# oled_pmic.net
KiCad netlist of a schematic drawn in EAGLE
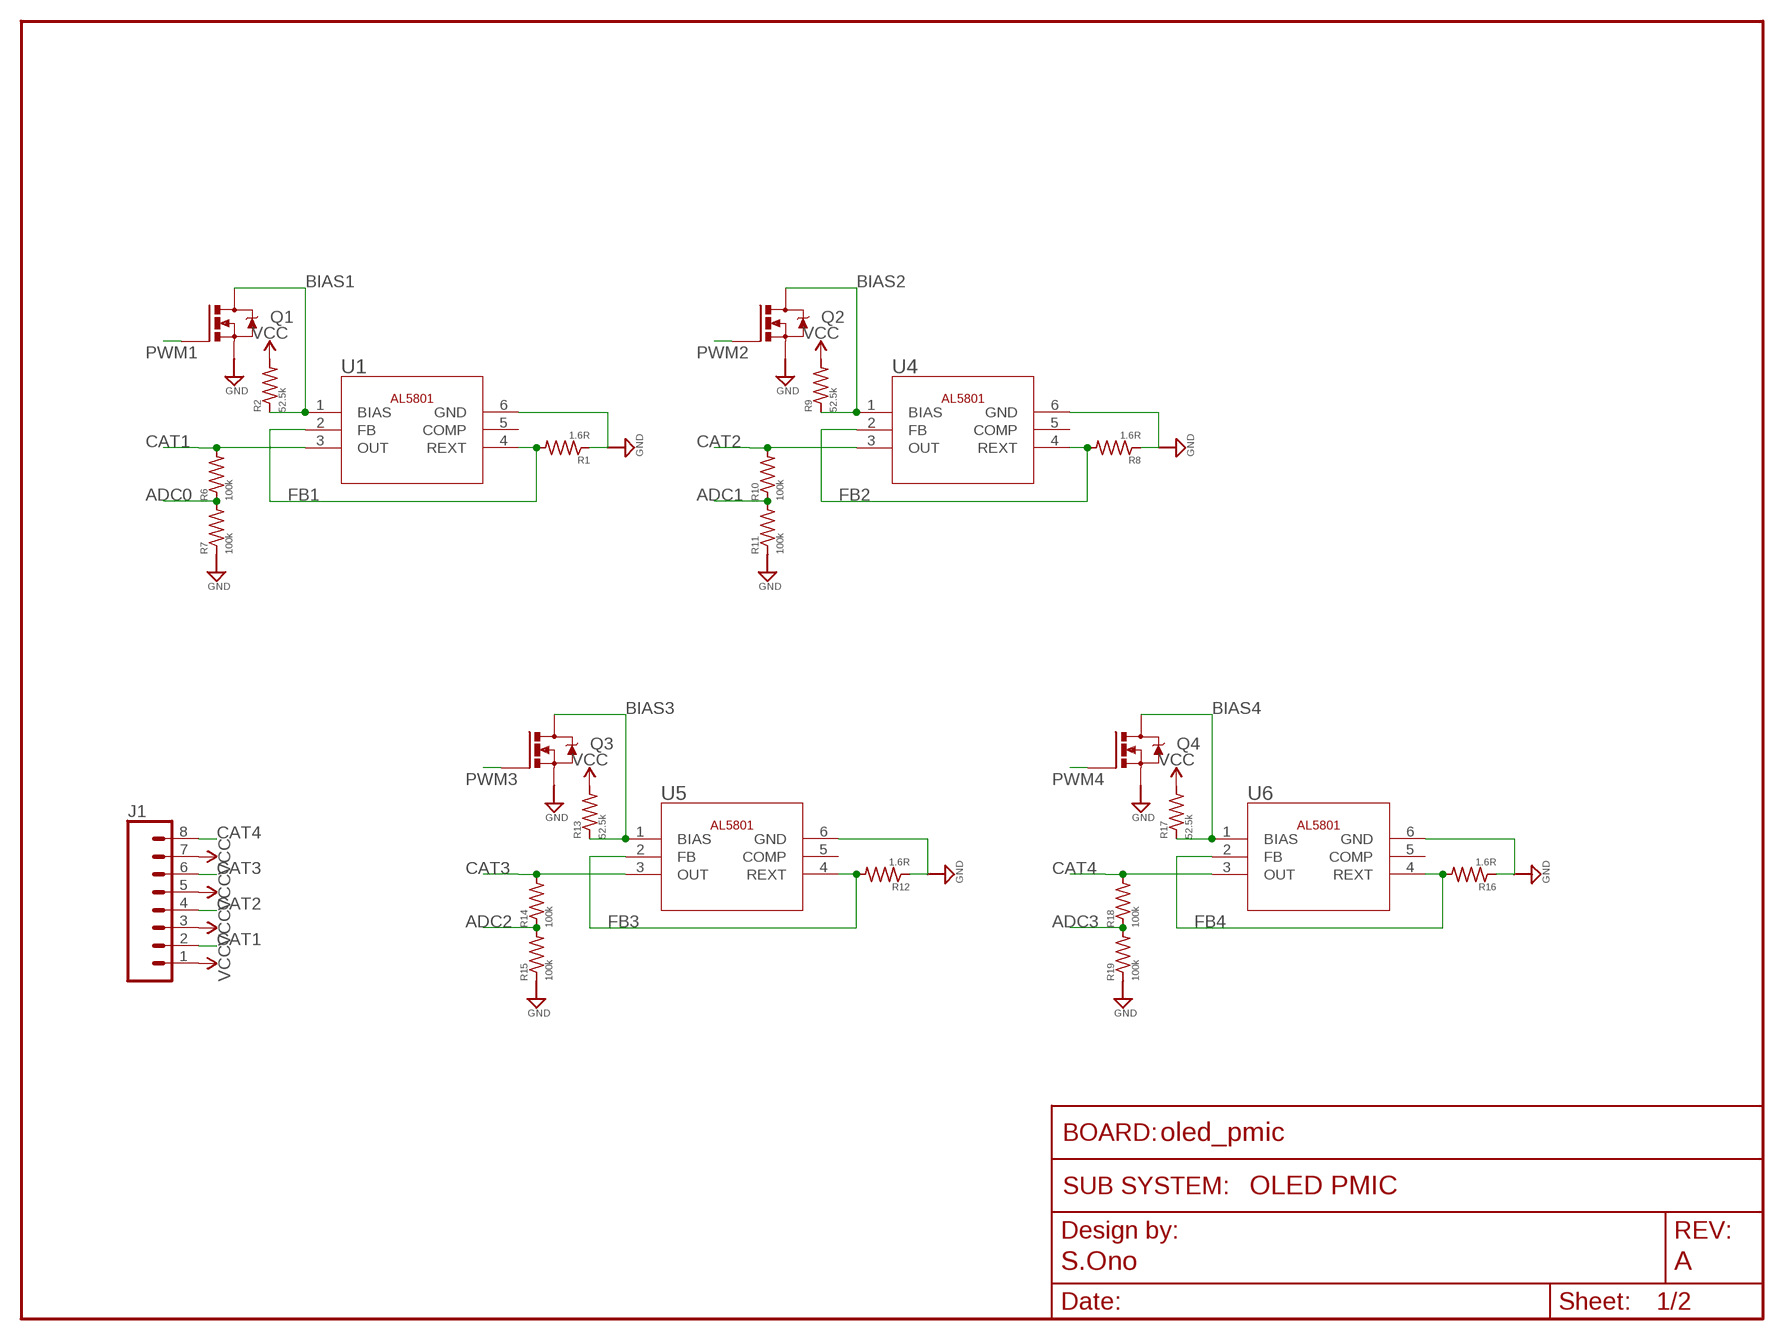
[diagram p0: schematic, sheet 1]
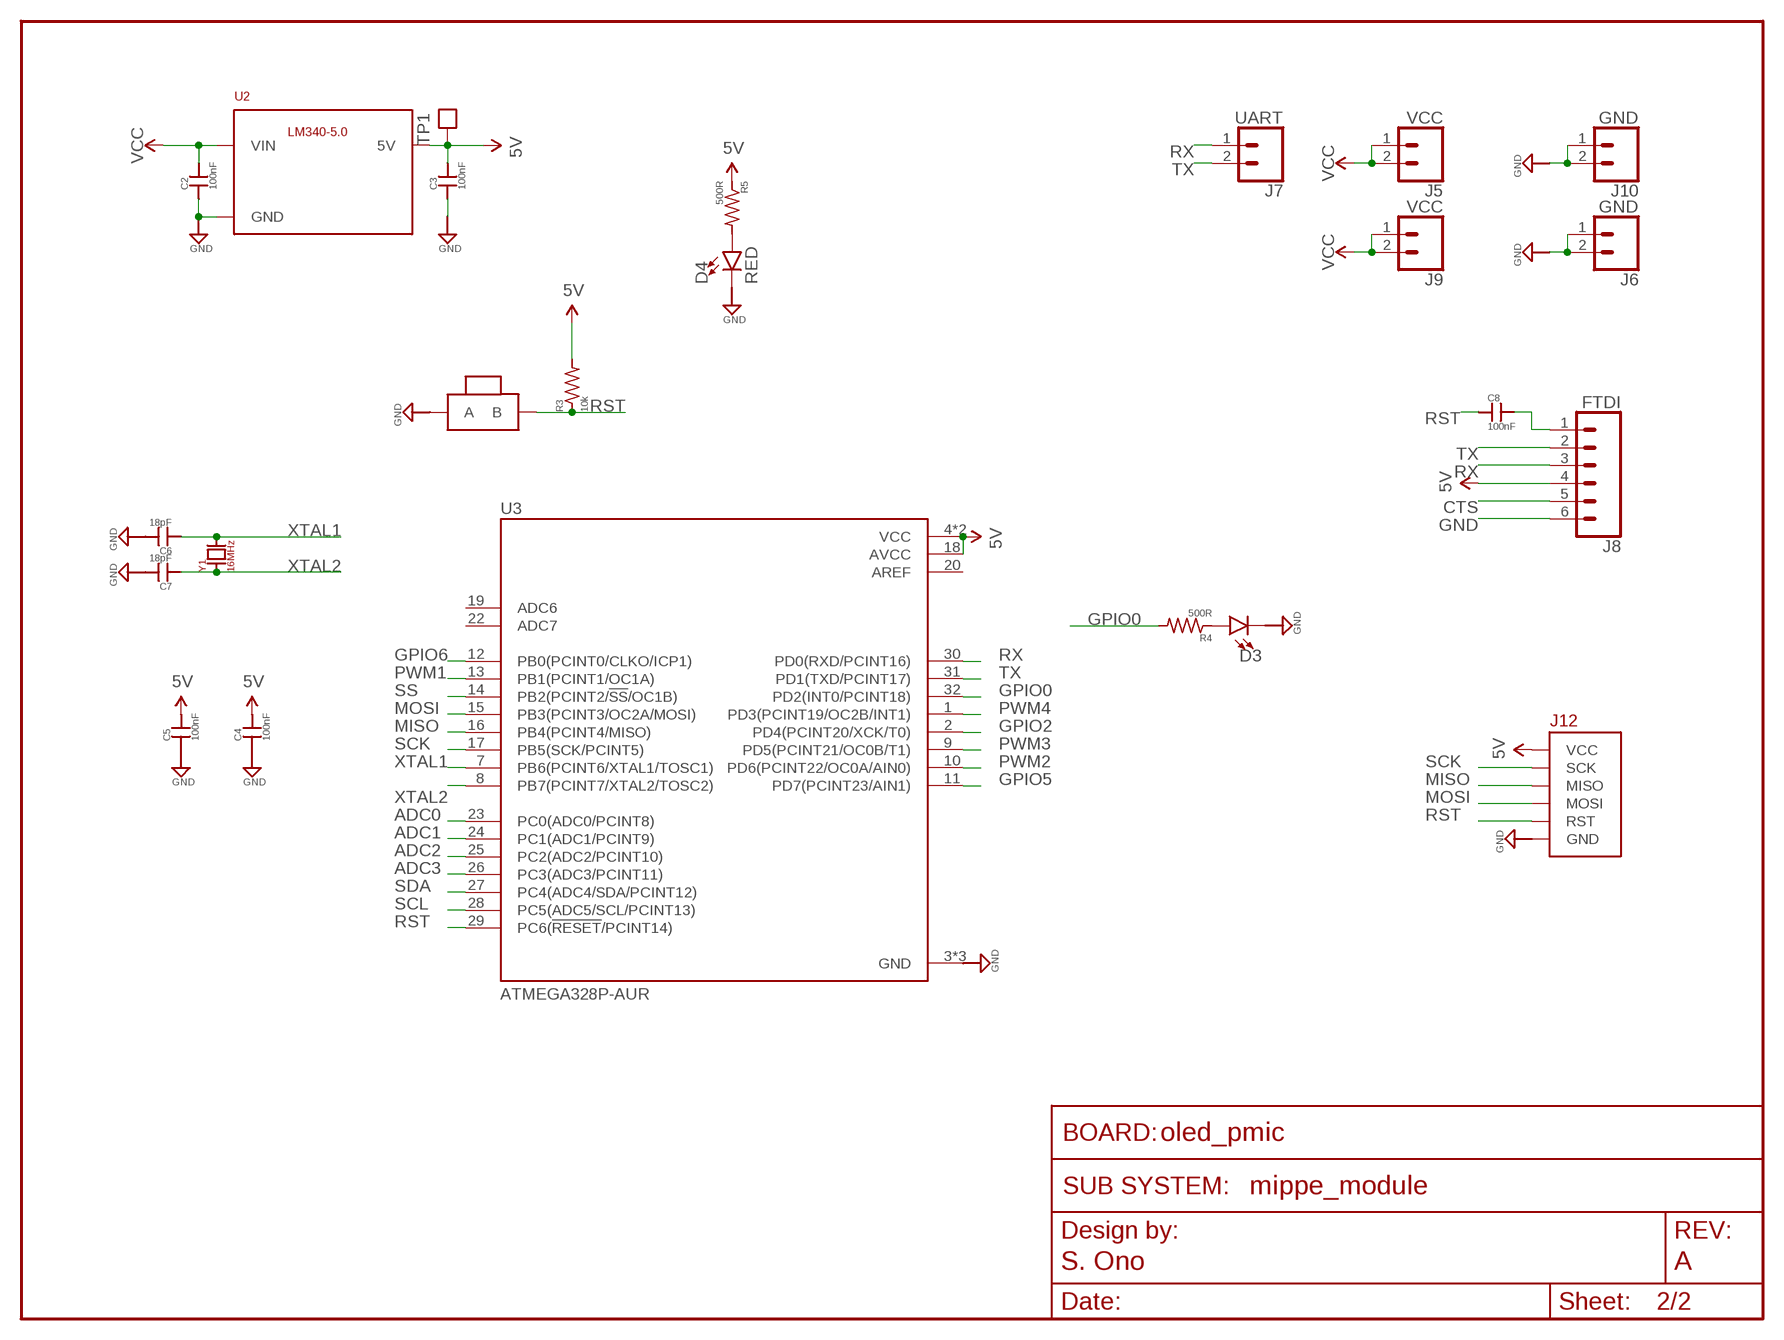
[diagram p1: schematic, sheet 2]

(export (version "E")
  (design (tool "Eeschema 10.0.6"))
  (components
    (comp (ref "C2")
      (value "100nF")
      (footprint "eagle-import:0402-CAP")
      (libsource (lib "eagle-import") (part "CAP0402-CAP"))
    )
    (comp (ref "C3")
      (value "100nF")
      (footprint "eagle-import:0402-CAP")
      (libsource (lib "eagle-import") (part "CAP0402-CAP"))
    )
    (comp (ref "C4")
      (value "100nF")
      (footprint "eagle-import:0402-CAP")
      (libsource (lib "eagle-import") (part "CAP0402-CAP"))
    )
    (comp (ref "C5")
      (value "100nF")
      (footprint "eagle-import:0402-CAP")
      (libsource (lib "eagle-import") (part "CAP0402-CAP"))
    )
    (comp (ref "C6")
      (value "18pF")
      (footprint "eagle-import:0402-CAP")
      (libsource (lib "eagle-import") (part "CAP0402-CAP"))
    )
    (comp (ref "C7")
      (value "18pF")
      (footprint "eagle-import:0402-CAP")
      (libsource (lib "eagle-import") (part "CAP0402-CAP"))
    )
    (comp (ref "C8")
      (value "100nF")
      (footprint "eagle-import:0402-CAP")
      (libsource (lib "eagle-import") (part "CAP0402-CAP"))
    )
    (comp (ref "D3")
      (value "LED0603")
      (footprint "eagle-import:LED-0603")
      (libsource (lib "eagle-import") (part "LED0603"))
    )
    (comp (ref "D4")
      (value "RED")
      (footprint "eagle-import:LED-0603")
      (libsource (lib "eagle-import") (part "LED0603"))
    )
    (comp (ref "J5")
      (value "VCC")
      (footprint "eagle-import:1X02")
      (libsource (lib "eagle-import") (part "CONN_02"))
    )
    (comp (ref "J6")
      (value "GND")
      (footprint "eagle-import:1X02")
      (libsource (lib "eagle-import") (part "CONN_02"))
    )
    (comp (ref "J7")
      (value "UART")
      (footprint "eagle-import:1X02")
      (libsource (lib "eagle-import") (part "CONN_02"))
    )
    (comp (ref "J8")
      (value "FTDI")
      (footprint "eagle-import:1X06_NO_SILK")
      (libsource (lib "eagle-import") (part "CONN_06NO_SILK_FEMALE_PTH"))
    )
    (comp (ref "J9")
      (value "VCC")
      (footprint "eagle-import:1X02")
      (libsource (lib "eagle-import") (part "CONN_02"))
    )
    (comp (ref "J10")
      (value "GND")
      (footprint "eagle-import:1X02")
      (libsource (lib "eagle-import") (part "CONN_02"))
    )
    (comp (ref "J12")
      (value "BURNIN")
      (footprint "eagle-import:BURNIN")
      (libsource (lib "eagle-import") (part "BURNIN"))
    )
    (comp (ref "R3")
      (value "10k")
      (footprint "eagle-import:R0402")
      (libsource (lib "eagle-import") (part "R-US_R0402"))
    )
    (comp (ref "R4")
      (value "500R")
      (footprint "eagle-import:R0402")
      (libsource (lib "eagle-import") (part "R-US_R0402"))
    )
    (comp (ref "R5")
      (value "500R")
      (footprint "eagle-import:R0402")
      (libsource (lib "eagle-import") (part "R-US_R0402"))
    )
    (comp (ref "SW1")
      (value "BTN-PTS810")
      (footprint "eagle-import:BTN_PTS810")
      (libsource (lib "eagle-import") (part "BTN-PTS810"))
    )
    (comp (ref "TP1")
      (value "TEST_POINTTHRU")
      (footprint "eagle-import:TEST_POINT")
      (libsource (lib "eagle-import") (part "TEST_POINTTHRU"))
    )
    (comp (ref "U2")
      (value "LM340MPX-5.0230")
      (footprint "eagle-import:SOT230P700X180-4N")
      (libsource (lib "eagle-import") (part "LM340MPX-5.0230"))
    )
    (comp (ref "U3")
      (value "ATMEGA328P-AUR")
      (footprint "eagle-import:QFP80P900X900X120-32N")
      (fields (field (name "DIGI-KEY_PART_NUMBER") "ATMEGA328P-AURCT-ND") (field (name "MF") "Microchip"))
      (libsource (lib "eagle-import") (part "ATMEGA328P-AUR"))
    )
    (comp (ref "Y1")
      (value "16MHz")
      (footprint "eagle-import:XTAL500X320X130N")
      (libsource (lib "eagle-import") (part "CRYSTAL_SMOL"))
    )
    (comp (ref "J1")
      (value "CONN_08\"")
      (footprint "eagle-import:1X08")
      (libsource (lib "eagle-import") (part "CONN_08{dblquote}"))
    )
    (comp (ref "Q1")
      (value "N-CHANNEL-MOSFETSOT23-3")
      (footprint "eagle-import:SOT23-3")
      (libsource (lib "eagle-import") (part "N-CHANNEL-MOSFETSOT23-3"))
    )
    (comp (ref "Q2")
      (value "N-CHANNEL-MOSFETSOT23-3")
      (footprint "eagle-import:SOT23-3")
      (libsource (lib "eagle-import") (part "N-CHANNEL-MOSFETSOT23-3"))
    )
    (comp (ref "Q3")
      (value "N-CHANNEL-MOSFETSOT23-3")
      (footprint "eagle-import:SOT23-3")
      (libsource (lib "eagle-import") (part "N-CHANNEL-MOSFETSOT23-3"))
    )
    (comp (ref "Q4")
      (value "N-CHANNEL-MOSFETSOT23-3")
      (footprint "eagle-import:SOT23-3")
      (libsource (lib "eagle-import") (part "N-CHANNEL-MOSFETSOT23-3"))
    )
    (comp (ref "R1")
      (value "1.6R")
      (footprint "eagle-import:0603-RES")
      (libsource (lib "eagle-import") (part "R-US_0603"))
    )
    (comp (ref "R2")
      (value "52.5k")
      (footprint "eagle-import:0603-RES")
      (libsource (lib "eagle-import") (part "R-US_0603"))
    )
    (comp (ref "R6")
      (value "100k")
      (footprint "eagle-import:R0402")
      (libsource (lib "eagle-import") (part "R-US_R0402"))
    )
    (comp (ref "R7")
      (value "100k")
      (footprint "eagle-import:R0402")
      (libsource (lib "eagle-import") (part "R-US_R0402"))
    )
    (comp (ref "R8")
      (value "1.6R")
      (footprint "eagle-import:0603-RES")
      (libsource (lib "eagle-import") (part "R-US_0603"))
    )
    (comp (ref "R9")
      (value "52.5k")
      (footprint "eagle-import:0603-RES")
      (libsource (lib "eagle-import") (part "R-US_0603"))
    )
    (comp (ref "R10")
      (value "100k")
      (footprint "eagle-import:R0402")
      (libsource (lib "eagle-import") (part "R-US_R0402"))
    )
    (comp (ref "R11")
      (value "100k")
      (footprint "eagle-import:R0402")
      (libsource (lib "eagle-import") (part "R-US_R0402"))
    )
    (comp (ref "R12")
      (value "1.6R")
      (footprint "eagle-import:0603-RES")
      (libsource (lib "eagle-import") (part "R-US_0603"))
    )
    (comp (ref "R13")
      (value "52.5k")
      (footprint "eagle-import:0603-RES")
      (libsource (lib "eagle-import") (part "R-US_0603"))
    )
    (comp (ref "R14")
      (value "100k")
      (footprint "eagle-import:R0402")
      (libsource (lib "eagle-import") (part "R-US_R0402"))
    )
    (comp (ref "R15")
      (value "100k")
      (footprint "eagle-import:R0402")
      (libsource (lib "eagle-import") (part "R-US_R0402"))
    )
    (comp (ref "R16")
      (value "1.6R")
      (footprint "eagle-import:0603-RES")
      (libsource (lib "eagle-import") (part "R-US_0603"))
    )
    (comp (ref "R17")
      (value "52.5k")
      (footprint "eagle-import:0603-RES")
      (libsource (lib "eagle-import") (part "R-US_0603"))
    )
    (comp (ref "R18")
      (value "100k")
      (footprint "eagle-import:R0402")
      (libsource (lib "eagle-import") (part "R-US_R0402"))
    )
    (comp (ref "R19")
      (value "100k")
      (footprint "eagle-import:R0402")
      (libsource (lib "eagle-import") (part "R-US_R0402"))
    )
    (comp (ref "U1")
      (value "AL5801W6-7")
      (footprint "eagle-import:SOT26")
      (libsource (lib "eagle-import") (part "AL5801W6-7"))
    )
    (comp (ref "U4")
      (value "AL5801W6-7")
      (footprint "eagle-import:SOT26")
      (libsource (lib "eagle-import") (part "AL5801W6-7"))
    )
    (comp (ref "U5")
      (value "AL5801W6-7")
      (footprint "eagle-import:SOT26")
      (libsource (lib "eagle-import") (part "AL5801W6-7"))
    )
    (comp (ref "U6")
      (value "AL5801W6-7")
      (footprint "eagle-import:SOT26")
      (libsource (lib "eagle-import") (part "AL5801W6-7"))
    )
  )
  (nets
    (net (code "1") (name "5V") (class "Default")
      (node (ref "C3") (pin "2") (pinfunction "2_2") (pintype "passive"))
      (node (ref "C4") (pin "2") (pinfunction "2_2") (pintype "passive"))
      (node (ref "C5") (pin "2") (pinfunction "2_2") (pintype "passive"))
      (node (ref "J12") (pin "3.3V") (pinfunction "VCC_3.3V") (pintype "power_in"))
      (node (ref "J8") (pin "4") (pinfunction "4_4") (pintype "passive"))
      (node (ref "R3") (pin "2") (pinfunction "2_2") (pintype "passive"))
      (node (ref "R5") (pin "1") (pinfunction "1_1") (pintype "passive"))
      (node (ref "TP1") (pin "1") (pinfunction "P$1_1") (pintype "bidirectional"))
      (node (ref "U2") (pin "3") (pinfunction "5V_3") (pintype "power_in"))
      (node (ref "U3") (pin "18") (pinfunction "AVCC_18") (pintype "power_in"))
      (node (ref "U3") (pin "4") (pinfunction "VCC_4") (pintype "power_in"))
      (node (ref "U3") (pin "6") (pinfunction "VCC_6") (pintype "power_in"))
    )
    (net (code "2") (name "ADC0") (class "Default")
      (node (ref "R6") (pin "1") (pinfunction "1_1") (pintype "passive"))
      (node (ref "R7") (pin "2") (pinfunction "2_2") (pintype "passive"))
      (node (ref "U3") (pin "23") (pinfunction "PC0(ADC0/PCINT8)_23") (pintype "bidirectional"))
    )
    (net (code "3") (name "ADC1") (class "Default")
      (node (ref "R10") (pin "1") (pinfunction "1_1") (pintype "passive"))
      (node (ref "R11") (pin "2") (pinfunction "2_2") (pintype "passive"))
      (node (ref "U3") (pin "24") (pinfunction "PC1(ADC1/PCINT9)_24") (pintype "bidirectional"))
    )
    (net (code "4") (name "ADC2") (class "Default")
      (node (ref "R14") (pin "1") (pinfunction "1_1") (pintype "passive"))
      (node (ref "R15") (pin "2") (pinfunction "2_2") (pintype "passive"))
      (node (ref "U3") (pin "25") (pinfunction "PC2(ADC2/PCINT10)_25") (pintype "bidirectional"))
    )
    (net (code "5") (name "ADC3") (class "Default")
      (node (ref "R18") (pin "1") (pinfunction "1_1") (pintype "passive"))
      (node (ref "R19") (pin "2") (pinfunction "2_2") (pintype "passive"))
      (node (ref "U3") (pin "26") (pinfunction "PC3(ADC3/PCINT11)_26") (pintype "bidirectional"))
    )
    (net (code "6") (name "AREF") (class "Default")
      (node (ref "U3") (pin "20") (pinfunction "AREF_20") (pintype "power_in"))
    )
    (net (code "7") (name "BIAS1") (class "Default")
      (node (ref "Q1") (pin "3") (pinfunction "D_3") (pintype "passive"))
      (node (ref "R2") (pin "1") (pinfunction "1_1") (pintype "passive"))
      (node (ref "U1") (pin "1") (pinfunction "BIAS_1") (pintype "output"))
    )
    (net (code "8") (name "BIAS2") (class "Default")
      (node (ref "Q2") (pin "3") (pinfunction "D_3") (pintype "passive"))
      (node (ref "R9") (pin "1") (pinfunction "1_1") (pintype "passive"))
      (node (ref "U4") (pin "1") (pinfunction "BIAS_1") (pintype "output"))
    )
    (net (code "9") (name "BIAS3") (class "Default")
      (node (ref "Q3") (pin "3") (pinfunction "D_3") (pintype "passive"))
      (node (ref "R13") (pin "1") (pinfunction "1_1") (pintype "passive"))
      (node (ref "U5") (pin "1") (pinfunction "BIAS_1") (pintype "output"))
    )
    (net (code "10") (name "BIAS4") (class "Default")
      (node (ref "Q4") (pin "3") (pinfunction "D_3") (pintype "passive"))
      (node (ref "R17") (pin "1") (pinfunction "1_1") (pintype "passive"))
      (node (ref "U6") (pin "1") (pinfunction "BIAS_1") (pintype "output"))
    )
    (net (code "11") (name "CAT1") (class "Default")
      (node (ref "J1") (pin "2") (pinfunction "2_2") (pintype "passive"))
      (node (ref "R6") (pin "2") (pinfunction "2_2") (pintype "passive"))
      (node (ref "U1") (pin "3") (pinfunction "OUT_3") (pintype "output"))
    )
    (net (code "12") (name "CAT2") (class "Default")
      (node (ref "J1") (pin "4") (pinfunction "4_4") (pintype "passive"))
      (node (ref "R10") (pin "2") (pinfunction "2_2") (pintype "passive"))
      (node (ref "U4") (pin "3") (pinfunction "OUT_3") (pintype "output"))
    )
    (net (code "13") (name "CAT3") (class "Default")
      (node (ref "J1") (pin "6") (pinfunction "6_6") (pintype "passive"))
      (node (ref "R14") (pin "2") (pinfunction "2_2") (pintype "passive"))
      (node (ref "U5") (pin "3") (pinfunction "OUT_3") (pintype "output"))
    )
    (net (code "14") (name "CAT4") (class "Default")
      (node (ref "J1") (pin "8") (pinfunction "8_8") (pintype "passive"))
      (node (ref "R18") (pin "2") (pinfunction "2_2") (pintype "passive"))
      (node (ref "U6") (pin "3") (pinfunction "OUT_3") (pintype "output"))
    )
    (net (code "15") (name "CTS") (class "Default")
      (node (ref "J8") (pin "5") (pinfunction "5_5") (pintype "passive"))
    )
    (net (code "16") (name "FB1") (class "Default")
      (node (ref "R1") (pin "2") (pinfunction "2_2") (pintype "passive"))
      (node (ref "U1") (pin "2") (pinfunction "FB_2") (pintype "passive"))
      (node (ref "U1") (pin "4") (pinfunction "REXT_4") (pintype "passive"))
    )
    (net (code "17") (name "FB2") (class "Default")
      (node (ref "R8") (pin "2") (pinfunction "2_2") (pintype "passive"))
      (node (ref "U4") (pin "2") (pinfunction "FB_2") (pintype "passive"))
      (node (ref "U4") (pin "4") (pinfunction "REXT_4") (pintype "passive"))
    )
    (net (code "18") (name "FB3") (class "Default")
      (node (ref "R12") (pin "2") (pinfunction "2_2") (pintype "passive"))
      (node (ref "U5") (pin "2") (pinfunction "FB_2") (pintype "passive"))
      (node (ref "U5") (pin "4") (pinfunction "REXT_4") (pintype "passive"))
    )
    (net (code "19") (name "FB4") (class "Default")
      (node (ref "R16") (pin "2") (pinfunction "2_2") (pintype "passive"))
      (node (ref "U6") (pin "2") (pinfunction "FB_2") (pintype "passive"))
      (node (ref "U6") (pin "4") (pinfunction "REXT_4") (pintype "passive"))
    )
    (net (code "20") (name "GND") (class "Default")
      (node (ref "C2") (pin "1") (pinfunction "1_1") (pintype "passive"))
      (node (ref "C3") (pin "1") (pinfunction "1_1") (pintype "passive"))
      (node (ref "C4") (pin "1") (pinfunction "1_1") (pintype "passive"))
      (node (ref "C5") (pin "1") (pinfunction "1_1") (pintype "passive"))
      (node (ref "C6") (pin "2") (pinfunction "2_2") (pintype "passive"))
      (node (ref "C7") (pin "2") (pinfunction "2_2") (pintype "passive"))
      (node (ref "D3") (pin "C") (pinfunction "C_C") (pintype "passive"))
      (node (ref "D4") (pin "C") (pinfunction "C_C") (pintype "passive"))
      (node (ref "J10") (pin "1") (pinfunction "1_1") (pintype "passive"))
      (node (ref "J10") (pin "2") (pinfunction "2_2") (pintype "passive"))
      (node (ref "J12") (pin "GND") (pinfunction "GND_GND") (pintype "power_in"))
      (node (ref "J6") (pin "1") (pinfunction "1_1") (pintype "passive"))
      (node (ref "J6") (pin "2") (pinfunction "2_2") (pintype "passive"))
      (node (ref "J8") (pin "6") (pinfunction "6_6") (pintype "passive"))
      (node (ref "Q1") (pin "2") (pinfunction "S_2") (pintype "passive"))
      (node (ref "Q2") (pin "2") (pinfunction "S_2") (pintype "passive"))
      (node (ref "Q3") (pin "2") (pinfunction "S_2") (pintype "passive"))
      (node (ref "Q4") (pin "2") (pinfunction "S_2") (pintype "passive"))
      (node (ref "R1") (pin "1") (pinfunction "1_1") (pintype "passive"))
      (node (ref "R11") (pin "1") (pinfunction "1_1") (pintype "passive"))
      (node (ref "R12") (pin "1") (pinfunction "1_1") (pintype "passive"))
      (node (ref "R15") (pin "1") (pinfunction "1_1") (pintype "passive"))
      (node (ref "R16") (pin "1") (pinfunction "1_1") (pintype "passive"))
      (node (ref "R19") (pin "1") (pinfunction "1_1") (pintype "passive"))
      (node (ref "R7") (pin "1") (pinfunction "1_1") (pintype "passive"))
      (node (ref "R8") (pin "1") (pinfunction "1_1") (pintype "passive"))
      (node (ref "SW1") (pin "1") (pinfunction "A_1") (pintype "bidirectional"))
      (node (ref "SW1") (pin "2") (pinfunction "A_2") (pintype "bidirectional"))
      (node (ref "U1") (pin "6") (pinfunction "GND_6") (pintype "power_in"))
      (node (ref "U2") (pin "2") (pinfunction "GND_2") (pintype "power_in"))
      (node (ref "U2") (pin "4") (pinfunction "GND_4") (pintype "power_in"))
      (node (ref "U3") (pin "21") (pinfunction "GND_21") (pintype "power_in"))
      (node (ref "U3") (pin "3") (pinfunction "GND_3") (pintype "power_in"))
      (node (ref "U3") (pin "5") (pinfunction "GND_5") (pintype "power_in"))
      (node (ref "U4") (pin "6") (pinfunction "GND_6") (pintype "power_in"))
      (node (ref "U5") (pin "6") (pinfunction "GND_6") (pintype "power_in"))
      (node (ref "U6") (pin "6") (pinfunction "GND_6") (pintype "power_in"))
    )
    (net (code "21") (name "GPIO0") (class "Default")
      (node (ref "R4") (pin "2") (pinfunction "2_2") (pintype "passive"))
      (node (ref "U3") (pin "32") (pinfunction "PD2(INT0/PCINT18)_32") (pintype "bidirectional"))
    )
    (net (code "22") (name "GPIO2") (class "Default")
      (node (ref "U3") (pin "2") (pinfunction "PD4(PCINT20/XCK/T0)_2") (pintype "bidirectional"))
    )
    (net (code "23") (name "GPIO5") (class "Default")
      (node (ref "U3") (pin "11") (pinfunction "PD7(PCINT23/AIN1)_11") (pintype "bidirectional"))
    )
    (net (code "24") (name "GPIO6") (class "Default")
      (node (ref "U3") (pin "12") (pinfunction "PB0(PCINT0/CLKO/ICP1)_12") (pintype "bidirectional"))
    )
    (net (code "25") (name "MISO") (class "Default")
      (node (ref "J12") (pin "MISO") (pinfunction "MISO_MISO") (pintype "bidirectional"))
      (node (ref "U3") (pin "16") (pinfunction "PB4(PCINT4/MISO)_16") (pintype "bidirectional"))
    )
    (net (code "26") (name "MOSI") (class "Default")
      (node (ref "J12") (pin "MOSI") (pinfunction "MOSI_MOSI") (pintype "bidirectional"))
      (node (ref "U3") (pin "15") (pinfunction "PB3(PCINT3/OC2A/MOSI)_15") (pintype "bidirectional"))
    )
    (net (code "27") (name "Net-(C8-Pad2)") (class "Default")
      (node (ref "C8") (pin "2") (pinfunction "2_2") (pintype "passive"))
      (node (ref "J8") (pin "1") (pinfunction "1_1") (pintype "passive"))
    )
    (net (code "28") (name "Net-(D3-PadA)") (class "Default")
      (node (ref "D3") (pin "A") (pinfunction "A_A") (pintype "passive"))
      (node (ref "R4") (pin "1") (pinfunction "1_1") (pintype "passive"))
    )
    (net (code "29") (name "Net-(D4-PadA)") (class "Default")
      (node (ref "D4") (pin "A") (pinfunction "A_A") (pintype "passive"))
      (node (ref "R5") (pin "2") (pinfunction "2_2") (pintype "passive"))
    )
    (net (code "30") (name "PWM1") (class "Default")
      (node (ref "Q1") (pin "1") (pinfunction "G_1") (pintype "passive"))
      (node (ref "U3") (pin "13") (pinfunction "PB1(PCINT1/OC1A)_13") (pintype "bidirectional"))
    )
    (net (code "31") (name "PWM2") (class "Default")
      (node (ref "Q2") (pin "1") (pinfunction "G_1") (pintype "passive"))
      (node (ref "U3") (pin "10") (pinfunction "PD6(PCINT22/OC0A/AIN0)_10") (pintype "bidirectional"))
    )
    (net (code "32") (name "PWM3") (class "Default")
      (node (ref "Q3") (pin "1") (pinfunction "G_1") (pintype "passive"))
      (node (ref "U3") (pin "9") (pinfunction "PD5(PCINT21/OC0B/T1)_9") (pintype "bidirectional"))
    )
    (net (code "33") (name "PWM4") (class "Default")
      (node (ref "Q4") (pin "1") (pinfunction "G_1") (pintype "passive"))
      (node (ref "U3") (pin "1") (pinfunction "PD3(PCINT19/OC2B/INT1)_1") (pintype "bidirectional"))
    )
    (net (code "34") (name "RST") (class "Default")
      (node (ref "C8") (pin "1") (pinfunction "1_1") (pintype "passive"))
      (node (ref "J12") (pin "RST") (pinfunction "RST_RST") (pintype "bidirectional"))
      (node (ref "R3") (pin "1") (pinfunction "1_1") (pintype "passive"))
      (node (ref "SW1") (pin "3") (pinfunction "B_3") (pintype "bidirectional"))
      (node (ref "SW1") (pin "4") (pinfunction "B_4") (pintype "bidirectional"))
      (node (ref "U3") (pin "29") (pinfunction "PC6(~{RESET}/PCINT14)_29") (pintype "bidirectional"))
    )
    (net (code "35") (name "RX") (class "Default")
      (node (ref "J7") (pin "1") (pinfunction "1_1") (pintype "passive"))
      (node (ref "J8") (pin "3") (pinfunction "3_3") (pintype "passive"))
      (node (ref "U3") (pin "30") (pinfunction "PD0(RXD/PCINT16)_30") (pintype "bidirectional"))
    )
    (net (code "36") (name "SCK") (class "Default")
      (node (ref "J12") (pin "SCK") (pinfunction "SCK_SCK") (pintype "bidirectional"))
      (node (ref "U3") (pin "17") (pinfunction "PB5(SCK/PCINT5)_17") (pintype "bidirectional"))
    )
    (net (code "37") (name "SCL") (class "Default")
      (node (ref "U3") (pin "28") (pinfunction "PC5(ADC5/SCL/PCINT13)_28") (pintype "bidirectional"))
    )
    (net (code "38") (name "SDA") (class "Default")
      (node (ref "U3") (pin "27") (pinfunction "PC4(ADC4/SDA/PCINT12)_27") (pintype "bidirectional"))
    )
    (net (code "39") (name "SS") (class "Default")
      (node (ref "U3") (pin "14") (pinfunction "PB2(PCINT2/~{SS}/OC1B)_14") (pintype "bidirectional"))
    )
    (net (code "40") (name "TX") (class "Default")
      (node (ref "J7") (pin "2") (pinfunction "2_2") (pintype "passive"))
      (node (ref "J8") (pin "2") (pinfunction "2_2") (pintype "passive"))
      (node (ref "U3") (pin "31") (pinfunction "PD1(TXD/PCINT17)_31") (pintype "bidirectional"))
    )
    (net (code "41") (name "VCC") (class "Default")
      (node (ref "C2") (pin "2") (pinfunction "2_2") (pintype "passive"))
      (node (ref "J1") (pin "1") (pinfunction "1_1") (pintype "passive"))
      (node (ref "J1") (pin "3") (pinfunction "3_3") (pintype "passive"))
      (node (ref "J1") (pin "5") (pinfunction "5_5") (pintype "passive"))
      (node (ref "J1") (pin "7") (pinfunction "7_7") (pintype "passive"))
      (node (ref "J5") (pin "1") (pinfunction "1_1") (pintype "passive"))
      (node (ref "J5") (pin "2") (pinfunction "2_2") (pintype "passive"))
      (node (ref "J9") (pin "1") (pinfunction "1_1") (pintype "passive"))
      (node (ref "J9") (pin "2") (pinfunction "2_2") (pintype "passive"))
      (node (ref "R13") (pin "2") (pinfunction "2_2") (pintype "passive"))
      (node (ref "R17") (pin "2") (pinfunction "2_2") (pintype "passive"))
      (node (ref "R2") (pin "2") (pinfunction "2_2") (pintype "passive"))
      (node (ref "R9") (pin "2") (pinfunction "2_2") (pintype "passive"))
      (node (ref "U2") (pin "1") (pinfunction "VIN_1") (pintype "power_in"))
    )
    (net (code "42") (name "XTAL1") (class "Default")
      (node (ref "C6") (pin "1") (pinfunction "1_1") (pintype "passive"))
      (node (ref "U3") (pin "7") (pinfunction "PB6(PCINT6/XTAL1/TOSC1)_7") (pintype "bidirectional"))
      (node (ref "Y1") (pin "2") (pinfunction "B_2") (pintype "passive"))
    )
    (net (code "43") (name "XTAL2") (class "Default")
      (node (ref "C7") (pin "1") (pinfunction "1_1") (pintype "passive"))
      (node (ref "U3") (pin "8") (pinfunction "PB7(PCINT7/XTAL2/TOSC2)_8") (pintype "bidirectional"))
      (node (ref "Y1") (pin "1") (pinfunction "A_1") (pintype "passive"))
    )
    (net (code "44") (name "unconnected-(U1-COMP-Pad5)") (class "Default")
      (node (ref "U1") (pin "5") (pinfunction "COMP_5") (pintype "passive"))
    )
    (net (code "45") (name "unconnected-(U3-ADC6-Pad19)") (class "Default")
      (node (ref "U3") (pin "19") (pinfunction "ADC6_19") (pintype "input"))
    )
    (net (code "46") (name "unconnected-(U3-ADC7-Pad22)") (class "Default")
      (node (ref "U3") (pin "22") (pinfunction "ADC7_22") (pintype "input"))
    )
    (net (code "47") (name "unconnected-(U4-COMP-Pad5)") (class "Default")
      (node (ref "U4") (pin "5") (pinfunction "COMP_5") (pintype "passive"))
    )
    (net (code "48") (name "unconnected-(U5-COMP-Pad5)") (class "Default")
      (node (ref "U5") (pin "5") (pinfunction "COMP_5") (pintype "passive"))
    )
    (net (code "49") (name "unconnected-(U6-COMP-Pad5)") (class "Default")
      (node (ref "U6") (pin "5") (pinfunction "COMP_5") (pintype "passive"))
    )
  )
)
